# D1_-_LCD_TH_Dupont.net
KiCad netlist of a schematic drawn in EAGLE
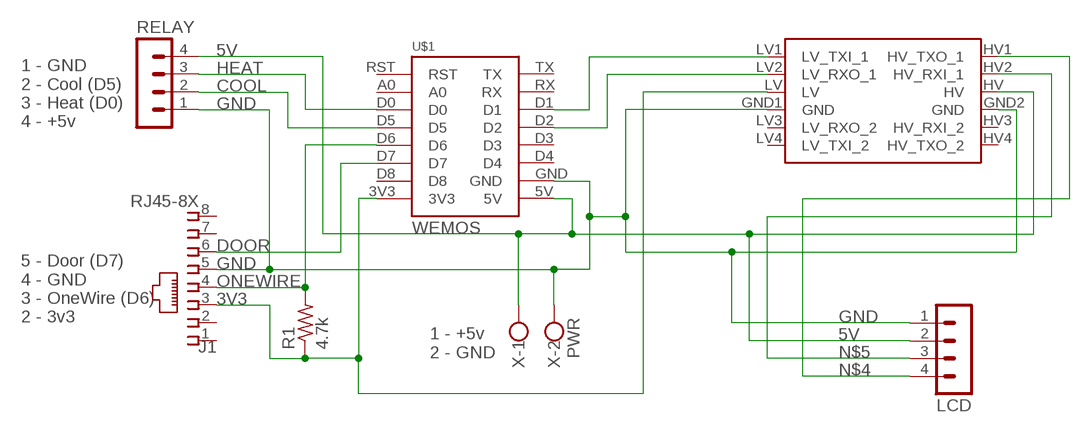
[diagram p0: schematic, sheet 1]

(export (version "E")
  (design (tool "Eeschema 10.0.6"))
  (components
    (comp (ref "J1")
      (value "RJ45-8X")
      (footprint "eagle-import:RJ45-NO-SHIELD")
      (libsource (lib "eagle-import") (part "RJ45-8X"))
    )
    (comp (ref "LCD")
      (value "MA04-1")
      (footprint "eagle-import:MA04-1")
      (libsource (lib "eagle-import") (part "MA04-1"))
    )
    (comp (ref "R1")
      (value "4.7k")
      (footprint "eagle-import:0309_12")
      (libsource (lib "eagle-import") (part "R-US_0309/12"))
    )
    (comp (ref "RELAY")
      (value "MA04-1")
      (footprint "eagle-import:MA04-1")
      (libsource (lib "eagle-import") (part "MA04-1"))
    )
    (comp (ref "U$1")
      (value "WEMOS")
      (footprint "eagle-import:WEMOS")
      (libsource (lib "eagle-import") (part "WEMOS"))
    )
    (comp (ref "U$3")
      (value "SPARKFUN_LOGIC_LEVEL_CONVERTER")
      (footprint "eagle-import:SPARKFUN_LOGIC_LEVEL_CONVERTER")
      (libsource (lib "eagle-import") (part "SPARKFUN_LOGIC_LEVEL_CONVERTER"))
    )
    (comp (ref "X")
      (value "PWR")
      (footprint "eagle-import:W237-102")
      (fields (field (name "MPN") "237-102"))
      (libsource (lib "eagle-import") (part "W237-102"))
    )
  )
  (nets
    (net (code "1") (name "/3V3") (class "Default")
      (node (ref "J1") (pin "3") (pinfunction "3_3") (pintype "passive"))
      (node (ref "R1") (pin "1") (pinfunction "1_1") (pintype "passive"))
      (node (ref "U$1") (pin "3V3") (pinfunction "3V3_3V3") (pintype "bidirectional"))
      (node (ref "U$3") (pin "LV") (pinfunction "LV_LV") (pintype "power_in"))
    )
    (net (code "2") (name "/5V") (class "Default")
      (node (ref "LCD") (pin "2") (pinfunction "2_2") (pintype "passive"))
      (node (ref "RELAY") (pin "4") (pinfunction "4_4") (pintype "passive"))
      (node (ref "U$1") (pin "5V") (pinfunction "5V_5V") (pintype "bidirectional"))
      (node (ref "U$3") (pin "HV") (pinfunction "HV_HV") (pintype "power_in"))
      (node (ref "X") (pin "1") (pinfunction "KL_1") (pintype "passive"))
    )
    (net (code "3") (name "/COOL") (class "Default")
      (node (ref "RELAY") (pin "2") (pinfunction "2_2") (pintype "passive"))
      (node (ref "U$1") (pin "D5") (pinfunction "D5_D5") (pintype "bidirectional"))
    )
    (net (code "4") (name "/DOOR") (class "Default")
      (node (ref "J1") (pin "6") (pinfunction "6_6") (pintype "passive"))
      (node (ref "U$1") (pin "D7") (pinfunction "D7_D7") (pintype "bidirectional"))
    )
    (net (code "5") (name "/GND") (class "Default")
      (node (ref "J1") (pin "5") (pinfunction "5_5") (pintype "passive"))
      (node (ref "LCD") (pin "1") (pinfunction "1_1") (pintype "passive"))
      (node (ref "RELAY") (pin "1") (pinfunction "1_1") (pintype "passive"))
      (node (ref "U$1") (pin "GND") (pinfunction "GND_GND") (pintype "bidirectional"))
      (node (ref "U$3") (pin "GND1") (pinfunction "GND_GND1") (pintype "power_in"))
      (node (ref "U$3") (pin "GND2") (pinfunction "GND_GND2") (pintype "power_in"))
      (node (ref "X") (pin "2") (pinfunction "KL_2") (pintype "passive"))
    )
    (net (code "6") (name "/HEAT") (class "Default")
      (node (ref "RELAY") (pin "3") (pinfunction "3_3") (pintype "passive"))
      (node (ref "U$1") (pin "D0") (pinfunction "D0_D0") (pintype "bidirectional"))
    )
    (net (code "7") (name "/N$4") (class "Default")
      (node (ref "LCD") (pin "4") (pinfunction "4_4") (pintype "passive"))
      (node (ref "U$3") (pin "HV1") (pinfunction "HV_TXO_1_HV1") (pintype "bidirectional"))
    )
    (net (code "8") (name "/N$5") (class "Default")
      (node (ref "LCD") (pin "3") (pinfunction "3_3") (pintype "passive"))
      (node (ref "U$3") (pin "HV2") (pinfunction "HV_RXI_1_HV2") (pintype "bidirectional"))
    )
    (net (code "9") (name "/ONEWIRE") (class "Default")
      (node (ref "J1") (pin "4") (pinfunction "4_4") (pintype "passive"))
      (node (ref "R1") (pin "2") (pinfunction "2_2") (pintype "passive"))
      (node (ref "U$1") (pin "D6") (pinfunction "D6_D6") (pintype "bidirectional"))
    )
    (net (code "10") (name "Net-(U$3-LV_RXO_1)") (class "Default")
      (node (ref "U$1") (pin "D2") (pinfunction "D2_D2") (pintype "bidirectional"))
      (node (ref "U$3") (pin "LV2") (pinfunction "LV_RXO_1_LV2") (pintype "bidirectional"))
    )
    (net (code "11") (name "Net-(U$3-LV_TXI_1)") (class "Default")
      (node (ref "U$1") (pin "D1") (pinfunction "D1_D1") (pintype "bidirectional"))
      (node (ref "U$3") (pin "LV1") (pinfunction "LV_TXI_1_LV1") (pintype "bidirectional"))
    )
    (net (code "12") (name "unconnected-(J1-Pad1)") (class "Default")
      (node (ref "J1") (pin "1") (pinfunction "1_1") (pintype "passive"))
    )
    (net (code "13") (name "unconnected-(J1-Pad2)") (class "Default")
      (node (ref "J1") (pin "2") (pinfunction "2_2") (pintype "passive"))
    )
    (net (code "14") (name "unconnected-(J1-Pad7)") (class "Default")
      (node (ref "J1") (pin "7") (pinfunction "7_7") (pintype "passive"))
    )
    (net (code "15") (name "unconnected-(J1-Pad8)") (class "Default")
      (node (ref "J1") (pin "8") (pinfunction "8_8") (pintype "passive"))
    )
    (net (code "16") (name "unconnected-(U$1-PadA0)") (class "Default")
      (node (ref "U$1") (pin "A0") (pinfunction "A0_A0") (pintype "bidirectional"))
    )
    (net (code "17") (name "unconnected-(U$1-PadD3)") (class "Default")
      (node (ref "U$1") (pin "D3") (pinfunction "D3_D3") (pintype "bidirectional"))
    )
    (net (code "18") (name "unconnected-(U$1-PadD4)") (class "Default")
      (node (ref "U$1") (pin "D4") (pinfunction "D4_D4") (pintype "bidirectional"))
    )
    (net (code "19") (name "unconnected-(U$1-PadD8)") (class "Default")
      (node (ref "U$1") (pin "D8") (pinfunction "D8_D8") (pintype "bidirectional"))
    )
    (net (code "20") (name "unconnected-(U$1-PadRST)") (class "Default")
      (node (ref "U$1") (pin "RST") (pinfunction "RST_RST") (pintype "bidirectional"))
    )
    (net (code "21") (name "unconnected-(U$1-PadRX)") (class "Default")
      (node (ref "U$1") (pin "RX") (pinfunction "RX_RX") (pintype "bidirectional"))
    )
    (net (code "22") (name "unconnected-(U$1-PadTX)") (class "Default")
      (node (ref "U$1") (pin "TX") (pinfunction "TX_TX") (pintype "bidirectional"))
    )
    (net (code "23") (name "unconnected-(U$3-HV_RXI_2-PadHV3)") (class "Default")
      (node (ref "U$3") (pin "HV3") (pinfunction "HV_RXI_2_HV3") (pintype "bidirectional"))
    )
    (net (code "24") (name "unconnected-(U$3-HV_TXO_2-PadHV4)") (class "Default")
      (node (ref "U$3") (pin "HV4") (pinfunction "HV_TXO_2_HV4") (pintype "bidirectional"))
    )
    (net (code "25") (name "unconnected-(U$3-LV_RXO_2-PadLV3)") (class "Default")
      (node (ref "U$3") (pin "LV3") (pinfunction "LV_RXO_2_LV3") (pintype "bidirectional"))
    )
    (net (code "26") (name "unconnected-(U$3-LV_TXI_2-PadLV4)") (class "Default")
      (node (ref "U$3") (pin "LV4") (pinfunction "LV_TXI_2_LV4") (pintype "bidirectional"))
    )
  )
)
